# Linkable_LED_Matrix.net
KiCad netlist of a schematic drawn in EAGLE
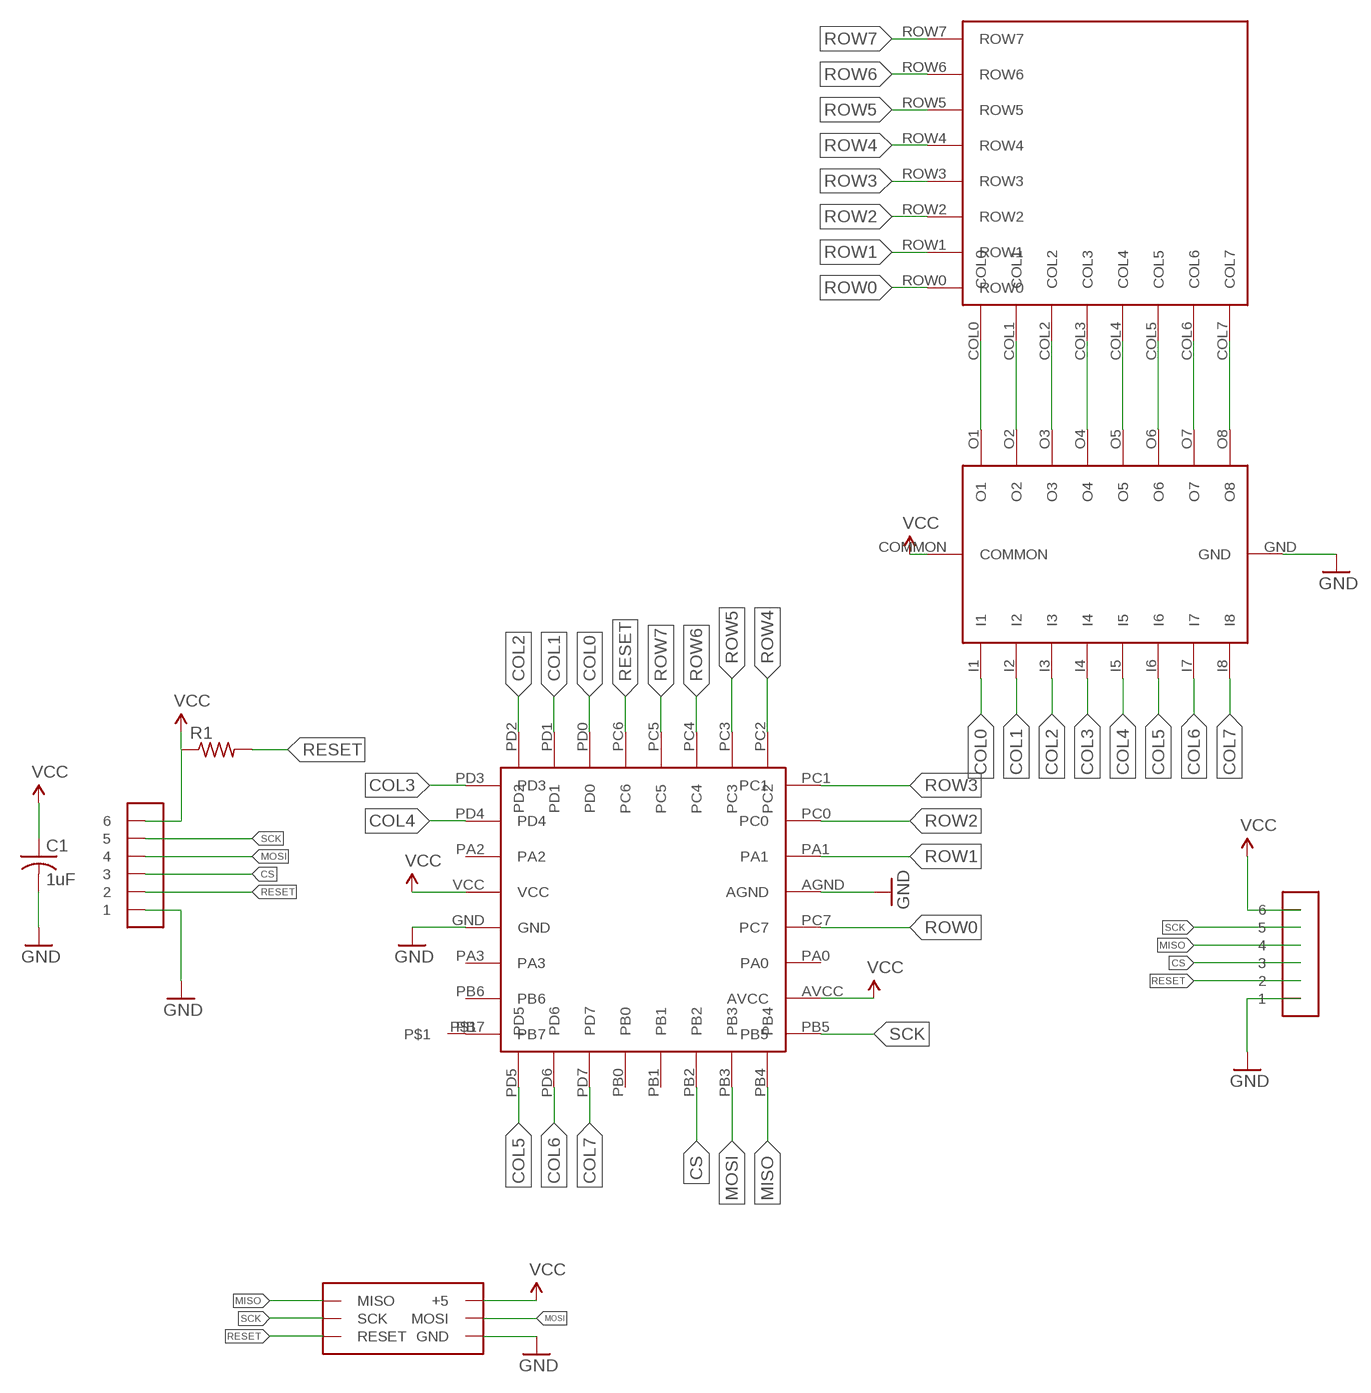
[diagram p0: schematic, sheet 1]

(export (version "E")
  (design (tool "Eeschema 10.0.6"))
  (components
    (comp (ref "C1")
      (value "1uF")
      (footprint "eagle-import:C0603")
      (libsource (lib "eagle-import") (part "C-USC0603"))
    )
    (comp (ref "R1")
      (value "R-US_R0603")
      (footprint "eagle-import:R0603")
      (libsource (lib "eagle-import") (part "R-US_R0603"))
    )
    (comp (ref "U$1")
      (value "ATTINY48")
      (footprint "eagle-import:ATTINY48")
      (libsource (lib "eagle-import") (part "ATTINY48"))
    )
    (comp (ref "U$2")
      (value "ULN2803AFWG")
      (footprint "eagle-import:ULN2803AFWG")
      (libsource (lib "eagle-import") (part "ULN2803AFWG"))
    )
    (comp (ref "U$3")
      (value "8X8_LED_MATRIX")
      (footprint "eagle-import:8X8_LED_MATRIX")
      (libsource (lib "eagle-import") (part "8X8_LED_MATRIX"))
    )
    (comp (ref "U$5")
      (value "1X1MM_PAD")
      (footprint "eagle-import:1X1MM_PAD")
      (libsource (lib "eagle-import") (part "1X1MM_PAD"))
    )
    (comp (ref "U$6")
      (value "DIP1X6MALE")
      (footprint "eagle-import:DIP1X6MALE")
      (libsource (lib "eagle-import") (part "DIP1X6MALE"))
    )
    (comp (ref "U$7")
      (value "DIP1X6MALE")
      (footprint "eagle-import:DIP1X6MALE")
      (libsource (lib "eagle-import") (part "DIP1X6MALE"))
    )
    (comp (ref "U$9")
      (value "DIP2X3MALE")
      (footprint "eagle-import:DIP2X3MALE")
      (libsource (lib "eagle-import") (part "DIP2X3MALE"))
    )
  )
  (nets
    (net (code "1") (name "COL0") (class "Default")
      (node (ref "U$1") (pin "PD0") (pinfunction "PD0_PD0") (pintype "bidirectional"))
      (node (ref "U$2") (pin "I1") (pinfunction "I1_I1") (pintype "bidirectional"))
    )
    (net (code "2") (name "COL1") (class "Default")
      (node (ref "U$1") (pin "PD1") (pinfunction "PD1_PD1") (pintype "bidirectional"))
      (node (ref "U$2") (pin "I2") (pinfunction "I2_I2") (pintype "bidirectional"))
    )
    (net (code "3") (name "COL2") (class "Default")
      (node (ref "U$1") (pin "PD2") (pinfunction "PD2_PD2") (pintype "bidirectional"))
      (node (ref "U$2") (pin "I3") (pinfunction "I3_I3") (pintype "bidirectional"))
    )
    (net (code "4") (name "COL3") (class "Default")
      (node (ref "U$1") (pin "PD3") (pinfunction "PD3_PD3") (pintype "bidirectional"))
      (node (ref "U$2") (pin "I4") (pinfunction "I4_I4") (pintype "bidirectional"))
    )
    (net (code "5") (name "COL4") (class "Default")
      (node (ref "U$1") (pin "PD4") (pinfunction "PD4_PD4") (pintype "bidirectional"))
      (node (ref "U$2") (pin "I5") (pinfunction "I5_I5") (pintype "bidirectional"))
    )
    (net (code "6") (name "COL5") (class "Default")
      (node (ref "U$1") (pin "PD5") (pinfunction "PD5_PD5") (pintype "bidirectional"))
      (node (ref "U$2") (pin "I6") (pinfunction "I6_I6") (pintype "bidirectional"))
    )
    (net (code "7") (name "COL6") (class "Default")
      (node (ref "U$1") (pin "PD6") (pinfunction "PD6_PD6") (pintype "bidirectional"))
      (node (ref "U$2") (pin "I7") (pinfunction "I7_I7") (pintype "bidirectional"))
    )
    (net (code "8") (name "COL7") (class "Default")
      (node (ref "U$1") (pin "PD7") (pinfunction "PD7_PD7") (pintype "bidirectional"))
      (node (ref "U$2") (pin "I8") (pinfunction "I8_I8") (pintype "bidirectional"))
    )
    (net (code "9") (name "CS") (class "Default")
      (node (ref "U$1") (pin "PB2") (pinfunction "PB2_PB2") (pintype "bidirectional"))
      (node (ref "U$6") (pin "3") (pinfunction "3_3") (pintype "bidirectional"))
      (node (ref "U$7") (pin "3") (pinfunction "3_3") (pintype "bidirectional"))
    )
    (net (code "10") (name "GND") (class "Default")
      (node (ref "C1") (pin "2") (pinfunction "2_2") (pintype "passive"))
      (node (ref "U$1") (pin "AGND") (pinfunction "AGND_AGND") (pintype "bidirectional"))
      (node (ref "U$1") (pin "GND") (pinfunction "GND_GND") (pintype "bidirectional"))
      (node (ref "U$2") (pin "GND") (pinfunction "GND_GND") (pintype "bidirectional"))
      (node (ref "U$6") (pin "1") (pinfunction "1_1") (pintype "bidirectional"))
      (node (ref "U$7") (pin "1") (pinfunction "1_1") (pintype "bidirectional"))
      (node (ref "U$9") (pin "GND") (pinfunction "GND_GND") (pintype "bidirectional"))
    )
    (net (code "11") (name "MISO") (class "Default")
      (node (ref "U$1") (pin "PB4") (pinfunction "PB4_PB4") (pintype "bidirectional"))
      (node (ref "U$7") (pin "4") (pinfunction "4_4") (pintype "bidirectional"))
      (node (ref "U$9") (pin "MISO") (pinfunction "MISO_MISO") (pintype "bidirectional"))
    )
    (net (code "12") (name "MOSI") (class "Default")
      (node (ref "U$1") (pin "PB3") (pinfunction "PB3_PB3") (pintype "bidirectional"))
      (node (ref "U$6") (pin "4") (pinfunction "4_4") (pintype "bidirectional"))
      (node (ref "U$9") (pin "MOSI") (pinfunction "MOSI_MOSI") (pintype "bidirectional"))
    )
    (net (code "13") (name "Net-(U$1-PadPB7)") (class "Default")
      (node (ref "U$1") (pin "PB7") (pinfunction "PB7_PB7") (pintype "bidirectional"))
      (node (ref "U$5") (pin "P$1") (pinfunction "P$1_P$1") (pintype "bidirectional"))
    )
    (net (code "14") (name "Net-(U$2-PadO1)") (class "Default")
      (node (ref "U$2") (pin "O1") (pinfunction "O1_O1") (pintype "bidirectional"))
      (node (ref "U$3") (pin "COL0") (pinfunction "COL0_COL0") (pintype "bidirectional"))
    )
    (net (code "15") (name "Net-(U$2-PadO2)") (class "Default")
      (node (ref "U$2") (pin "O2") (pinfunction "O2_O2") (pintype "bidirectional"))
      (node (ref "U$3") (pin "COL1") (pinfunction "COL1_COL1") (pintype "bidirectional"))
    )
    (net (code "16") (name "Net-(U$2-PadO3)") (class "Default")
      (node (ref "U$2") (pin "O3") (pinfunction "O3_O3") (pintype "bidirectional"))
      (node (ref "U$3") (pin "COL2") (pinfunction "COL2_COL2") (pintype "bidirectional"))
    )
    (net (code "17") (name "Net-(U$2-PadO4)") (class "Default")
      (node (ref "U$2") (pin "O4") (pinfunction "O4_O4") (pintype "bidirectional"))
      (node (ref "U$3") (pin "COL3") (pinfunction "COL3_COL3") (pintype "bidirectional"))
    )
    (net (code "18") (name "Net-(U$2-PadO5)") (class "Default")
      (node (ref "U$2") (pin "O5") (pinfunction "O5_O5") (pintype "bidirectional"))
      (node (ref "U$3") (pin "COL4") (pinfunction "COL4_COL4") (pintype "bidirectional"))
    )
    (net (code "19") (name "Net-(U$2-PadO6)") (class "Default")
      (node (ref "U$2") (pin "O6") (pinfunction "O6_O6") (pintype "bidirectional"))
      (node (ref "U$3") (pin "COL5") (pinfunction "COL5_COL5") (pintype "bidirectional"))
    )
    (net (code "20") (name "Net-(U$2-PadO7)") (class "Default")
      (node (ref "U$2") (pin "O7") (pinfunction "O7_O7") (pintype "bidirectional"))
      (node (ref "U$3") (pin "COL6") (pinfunction "COL6_COL6") (pintype "bidirectional"))
    )
    (net (code "21") (name "Net-(U$2-PadO8)") (class "Default")
      (node (ref "U$2") (pin "O8") (pinfunction "O8_O8") (pintype "bidirectional"))
      (node (ref "U$3") (pin "COL7") (pinfunction "COL7_COL7") (pintype "bidirectional"))
    )
    (net (code "22") (name "RESET") (class "Default")
      (node (ref "R1") (pin "2") (pinfunction "2_2") (pintype "passive"))
      (node (ref "U$1") (pin "PC6") (pinfunction "PC6_PC6") (pintype "bidirectional"))
      (node (ref "U$6") (pin "2") (pinfunction "2_2") (pintype "bidirectional"))
      (node (ref "U$7") (pin "2") (pinfunction "2_2") (pintype "bidirectional"))
      (node (ref "U$9") (pin "RESET") (pinfunction "RESET_RESET") (pintype "bidirectional"))
    )
    (net (code "23") (name "ROW0") (class "Default")
      (node (ref "U$1") (pin "PC7") (pinfunction "PC7_PC7") (pintype "bidirectional"))
      (node (ref "U$3") (pin "ROW0") (pinfunction "ROW0_ROW0") (pintype "bidirectional"))
    )
    (net (code "24") (name "ROW1") (class "Default")
      (node (ref "U$1") (pin "PA1") (pinfunction "PA1_PA1") (pintype "bidirectional"))
      (node (ref "U$3") (pin "ROW1") (pinfunction "ROW1_ROW1") (pintype "bidirectional"))
    )
    (net (code "25") (name "ROW2") (class "Default")
      (node (ref "U$1") (pin "PC0") (pinfunction "PC0_PC0") (pintype "bidirectional"))
      (node (ref "U$3") (pin "ROW2") (pinfunction "ROW2_ROW2") (pintype "bidirectional"))
    )
    (net (code "26") (name "ROW3") (class "Default")
      (node (ref "U$1") (pin "PC1") (pinfunction "PC1_PC1") (pintype "bidirectional"))
      (node (ref "U$3") (pin "ROW3") (pinfunction "ROW3_ROW3") (pintype "bidirectional"))
    )
    (net (code "27") (name "ROW4") (class "Default")
      (node (ref "U$1") (pin "PC2") (pinfunction "PC2_PC2") (pintype "bidirectional"))
      (node (ref "U$3") (pin "ROW4") (pinfunction "ROW4_ROW4") (pintype "bidirectional"))
    )
    (net (code "28") (name "ROW5") (class "Default")
      (node (ref "U$1") (pin "PC3") (pinfunction "PC3_PC3") (pintype "bidirectional"))
      (node (ref "U$3") (pin "ROW5") (pinfunction "ROW5_ROW5") (pintype "bidirectional"))
    )
    (net (code "29") (name "ROW6") (class "Default")
      (node (ref "U$1") (pin "PC4") (pinfunction "PC4_PC4") (pintype "bidirectional"))
      (node (ref "U$3") (pin "ROW6") (pinfunction "ROW6_ROW6") (pintype "bidirectional"))
    )
    (net (code "30") (name "ROW7") (class "Default")
      (node (ref "U$1") (pin "PC5") (pinfunction "PC5_PC5") (pintype "bidirectional"))
      (node (ref "U$3") (pin "ROW7") (pinfunction "ROW7_ROW7") (pintype "bidirectional"))
    )
    (net (code "31") (name "SCK") (class "Default")
      (node (ref "U$1") (pin "PB5") (pinfunction "PB5_PB5") (pintype "bidirectional"))
      (node (ref "U$6") (pin "5") (pinfunction "5_5") (pintype "bidirectional"))
      (node (ref "U$7") (pin "5") (pinfunction "5_5") (pintype "bidirectional"))
      (node (ref "U$9") (pin "SCK") (pinfunction "SCK_SCK") (pintype "bidirectional"))
    )
    (net (code "32") (name "VCC") (class "Default")
      (node (ref "C1") (pin "1") (pinfunction "1_1") (pintype "passive"))
      (node (ref "R1") (pin "1") (pinfunction "1_1") (pintype "passive"))
      (node (ref "U$1") (pin "AVCC") (pinfunction "AVCC_AVCC") (pintype "bidirectional"))
      (node (ref "U$1") (pin "VCC") (pinfunction "VCC_VCC") (pintype "bidirectional"))
      (node (ref "U$2") (pin "COMMON") (pinfunction "COMMON_COMMON") (pintype "bidirectional"))
      (node (ref "U$6") (pin "6") (pinfunction "6_6") (pintype "bidirectional"))
      (node (ref "U$7") (pin "6") (pinfunction "6_6") (pintype "bidirectional"))
      (node (ref "U$9") (pin "5V") (pinfunction "+5_5V") (pintype "bidirectional"))
    )
    (net (code "33") (name "unconnected-(U$1-PadPA0)") (class "Default")
      (node (ref "U$1") (pin "PA0") (pinfunction "PA0_PA0") (pintype "bidirectional"))
    )
    (net (code "34") (name "unconnected-(U$1-PadPA2)") (class "Default")
      (node (ref "U$1") (pin "PA2") (pinfunction "PA2_PA2") (pintype "bidirectional"))
    )
    (net (code "35") (name "unconnected-(U$1-PadPA3)") (class "Default")
      (node (ref "U$1") (pin "PA3") (pinfunction "PA3_PA3") (pintype "bidirectional"))
    )
    (net (code "36") (name "unconnected-(U$1-PadPB0)") (class "Default")
      (node (ref "U$1") (pin "PB0") (pinfunction "PB0_PB0") (pintype "bidirectional"))
    )
    (net (code "37") (name "unconnected-(U$1-PadPB1)") (class "Default")
      (node (ref "U$1") (pin "PB1") (pinfunction "PB1_PB1") (pintype "bidirectional"))
    )
    (net (code "38") (name "unconnected-(U$1-PadPB6)") (class "Default")
      (node (ref "U$1") (pin "PB6") (pinfunction "PB6_PB6") (pintype "bidirectional"))
    )
  )
)
